# terra_o_verde_placa_perfurada_com_pluvio.net
KiCad netlist of a schematic drawn in EAGLE
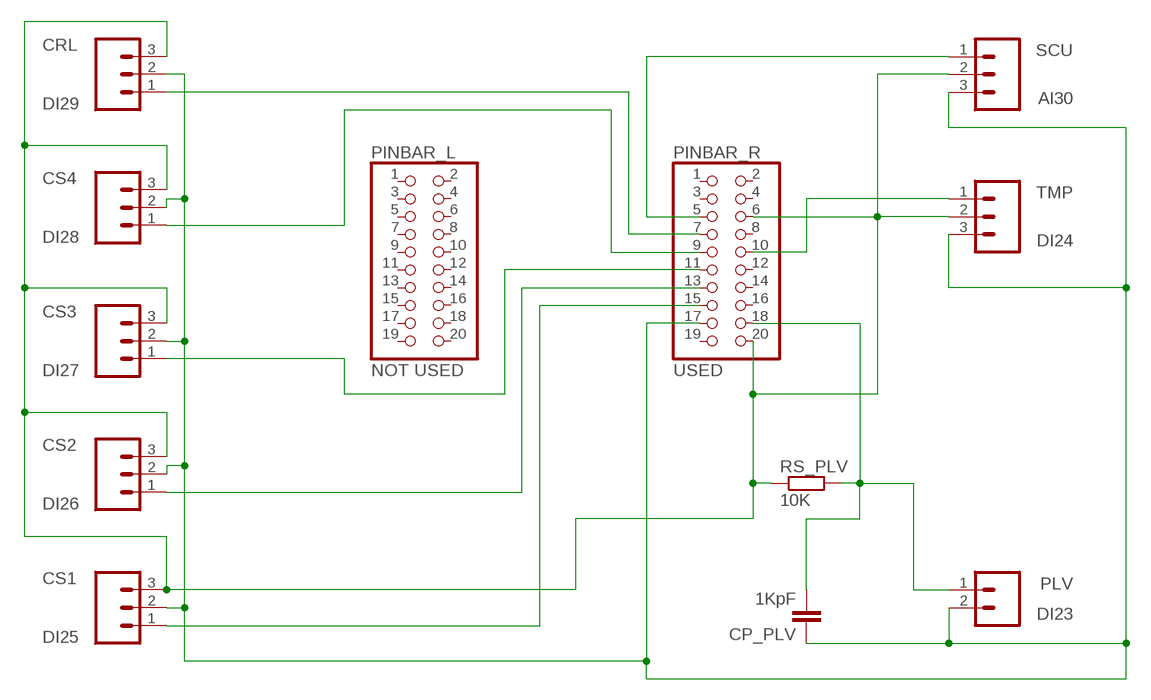
[diagram p0: schematic, sheet 1]

(export (version "E")
  (design (tool "Eeschema 10.0.6"))
  (components
    (comp (ref "CP_PLV")
      (value "1KpF")
      (footprint "eagle-import:C025-024X044")
      (libsource (lib "eagle-import") (part "C-EU025-024X044"))
    )
    (comp (ref "CRL")
      (value "DI29")
      (footprint "eagle-import:03P")
      (libsource (lib "eagle-import") (part "M03"))
    )
    (comp (ref "CS1")
      (value "DI25")
      (footprint "eagle-import:03P")
      (libsource (lib "eagle-import") (part "M03"))
    )
    (comp (ref "CS2")
      (value "DI26")
      (footprint "eagle-import:03P")
      (libsource (lib "eagle-import") (part "M03"))
    )
    (comp (ref "CS3")
      (value "DI27")
      (footprint "eagle-import:03P")
      (libsource (lib "eagle-import") (part "M03"))
    )
    (comp (ref "CS4")
      (value "DI28")
      (footprint "eagle-import:03P")
      (libsource (lib "eagle-import") (part "M03"))
    )
    (comp (ref "PINBAR_L")
      (value "NOT USED")
      (footprint "eagle-import:2X10")
      (libsource (lib "eagle-import") (part "PINHD-2X10"))
    )
    (comp (ref "PINBAR_R")
      (value "USED")
      (footprint "eagle-import:2X10")
      (libsource (lib "eagle-import") (part "PINHD-2X10"))
    )
    (comp (ref "PLV")
      (value "DI23")
      (footprint "eagle-import:02P")
      (libsource (lib "eagle-import") (part "M02"))
    )
    (comp (ref "RS_PLV")
      (value "10K")
      (footprint "eagle-import:0207_7")
      (libsource (lib "eagle-import") (part "R-EU_0207/7"))
    )
    (comp (ref "SCU")
      (value "AI30")
      (footprint "eagle-import:03P")
      (libsource (lib "eagle-import") (part "M03"))
    )
    (comp (ref "TMP")
      (value "DI24")
      (footprint "eagle-import:03P")
      (libsource (lib "eagle-import") (part "M03"))
    )
  )
  (nets
    (net (code "1") (name "Net-(CP_PLV-Pad1)") (class "Default")
      (node (ref "CP_PLV") (pin "1") (pinfunction "1_1") (pintype "passive"))
      (node (ref "CRL") (pin "2") (pinfunction "2_2") (pintype "passive"))
      (node (ref "CS1") (pin "2") (pinfunction "2_2") (pintype "passive"))
      (node (ref "CS2") (pin "2") (pinfunction "2_2") (pintype "passive"))
      (node (ref "CS3") (pin "2") (pinfunction "2_2") (pintype "passive"))
      (node (ref "CS4") (pin "2") (pinfunction "2_2") (pintype "passive"))
      (node (ref "PINBAR_R") (pin "17") (pinfunction "17_17") (pintype "passive"))
      (node (ref "PLV") (pin "2") (pinfunction "2_2") (pintype "passive"))
      (node (ref "SCU") (pin "3") (pinfunction "3_3") (pintype "passive"))
      (node (ref "TMP") (pin "3") (pinfunction "3_3") (pintype "passive"))
    )
    (net (code "2") (name "Net-(CP_PLV-Pad2)") (class "Default")
      (node (ref "CP_PLV") (pin "2") (pinfunction "2_2") (pintype "passive"))
      (node (ref "PINBAR_R") (pin "18") (pinfunction "18_18") (pintype "passive"))
      (node (ref "PLV") (pin "1") (pinfunction "1_1") (pintype "passive"))
      (node (ref "RS_PLV") (pin "2") (pinfunction "2_2") (pintype "passive"))
    )
    (net (code "3") (name "Net-(CRL-Pad1)") (class "Default")
      (node (ref "CRL") (pin "1") (pinfunction "1_1") (pintype "passive"))
      (node (ref "PINBAR_R") (pin "7") (pinfunction "7_7") (pintype "passive"))
    )
    (net (code "4") (name "Net-(CRL-Pad3)") (class "Default")
      (node (ref "CRL") (pin "3") (pinfunction "3_3") (pintype "passive"))
      (node (ref "CS1") (pin "3") (pinfunction "3_3") (pintype "passive"))
      (node (ref "CS2") (pin "3") (pinfunction "3_3") (pintype "passive"))
      (node (ref "CS3") (pin "3") (pinfunction "3_3") (pintype "passive"))
      (node (ref "CS4") (pin "3") (pinfunction "3_3") (pintype "passive"))
      (node (ref "PINBAR_R") (pin "20") (pinfunction "20_20") (pintype "passive"))
      (node (ref "PINBAR_R") (pin "6") (pinfunction "6_6") (pintype "passive"))
      (node (ref "RS_PLV") (pin "1") (pinfunction "1_1") (pintype "passive"))
      (node (ref "SCU") (pin "2") (pinfunction "2_2") (pintype "passive"))
      (node (ref "TMP") (pin "2") (pinfunction "2_2") (pintype "passive"))
    )
    (net (code "5") (name "Net-(CS1-Pad1)") (class "Default")
      (node (ref "CS1") (pin "1") (pinfunction "1_1") (pintype "passive"))
      (node (ref "PINBAR_R") (pin "15") (pinfunction "15_15") (pintype "passive"))
    )
    (net (code "6") (name "Net-(CS2-Pad1)") (class "Default")
      (node (ref "CS2") (pin "1") (pinfunction "1_1") (pintype "passive"))
      (node (ref "PINBAR_R") (pin "13") (pinfunction "13_13") (pintype "passive"))
    )
    (net (code "7") (name "Net-(CS3-Pad1)") (class "Default")
      (node (ref "CS3") (pin "1") (pinfunction "1_1") (pintype "passive"))
      (node (ref "PINBAR_R") (pin "11") (pinfunction "11_11") (pintype "passive"))
    )
    (net (code "8") (name "Net-(CS4-Pad1)") (class "Default")
      (node (ref "CS4") (pin "1") (pinfunction "1_1") (pintype "passive"))
      (node (ref "PINBAR_R") (pin "9") (pinfunction "9_9") (pintype "passive"))
    )
    (net (code "9") (name "Net-(PINBAR_R-Pad5)") (class "Default")
      (node (ref "PINBAR_R") (pin "5") (pinfunction "5_5") (pintype "passive"))
      (node (ref "SCU") (pin "1") (pinfunction "1_1") (pintype "passive"))
    )
    (net (code "10") (name "Net-(PINBAR_R-Pad10)") (class "Default")
      (node (ref "PINBAR_R") (pin "10") (pinfunction "10_10") (pintype "passive"))
      (node (ref "TMP") (pin "1") (pinfunction "1_1") (pintype "passive"))
    )
    (net (code "11") (name "unconnected-(PINBAR_L-Pad1)") (class "Default")
      (node (ref "PINBAR_L") (pin "1") (pinfunction "1_1") (pintype "passive"))
    )
    (net (code "12") (name "unconnected-(PINBAR_L-Pad2)") (class "Default")
      (node (ref "PINBAR_L") (pin "2") (pinfunction "2_2") (pintype "passive"))
    )
    (net (code "13") (name "unconnected-(PINBAR_L-Pad3)") (class "Default")
      (node (ref "PINBAR_L") (pin "3") (pinfunction "3_3") (pintype "passive"))
    )
    (net (code "14") (name "unconnected-(PINBAR_L-Pad4)") (class "Default")
      (node (ref "PINBAR_L") (pin "4") (pinfunction "4_4") (pintype "passive"))
    )
    (net (code "15") (name "unconnected-(PINBAR_L-Pad5)") (class "Default")
      (node (ref "PINBAR_L") (pin "5") (pinfunction "5_5") (pintype "passive"))
    )
    (net (code "16") (name "unconnected-(PINBAR_L-Pad6)") (class "Default")
      (node (ref "PINBAR_L") (pin "6") (pinfunction "6_6") (pintype "passive"))
    )
    (net (code "17") (name "unconnected-(PINBAR_L-Pad7)") (class "Default")
      (node (ref "PINBAR_L") (pin "7") (pinfunction "7_7") (pintype "passive"))
    )
    (net (code "18") (name "unconnected-(PINBAR_L-Pad8)") (class "Default")
      (node (ref "PINBAR_L") (pin "8") (pinfunction "8_8") (pintype "passive"))
    )
    (net (code "19") (name "unconnected-(PINBAR_L-Pad9)") (class "Default")
      (node (ref "PINBAR_L") (pin "9") (pinfunction "9_9") (pintype "passive"))
    )
    (net (code "20") (name "unconnected-(PINBAR_L-Pad10)") (class "Default")
      (node (ref "PINBAR_L") (pin "10") (pinfunction "10_10") (pintype "passive"))
    )
    (net (code "21") (name "unconnected-(PINBAR_L-Pad11)") (class "Default")
      (node (ref "PINBAR_L") (pin "11") (pinfunction "11_11") (pintype "passive"))
    )
    (net (code "22") (name "unconnected-(PINBAR_L-Pad12)") (class "Default")
      (node (ref "PINBAR_L") (pin "12") (pinfunction "12_12") (pintype "passive"))
    )
    (net (code "23") (name "unconnected-(PINBAR_L-Pad13)") (class "Default")
      (node (ref "PINBAR_L") (pin "13") (pinfunction "13_13") (pintype "passive"))
    )
    (net (code "24") (name "unconnected-(PINBAR_L-Pad14)") (class "Default")
      (node (ref "PINBAR_L") (pin "14") (pinfunction "14_14") (pintype "passive"))
    )
    (net (code "25") (name "unconnected-(PINBAR_L-Pad15)") (class "Default")
      (node (ref "PINBAR_L") (pin "15") (pinfunction "15_15") (pintype "passive"))
    )
    (net (code "26") (name "unconnected-(PINBAR_L-Pad16)") (class "Default")
      (node (ref "PINBAR_L") (pin "16") (pinfunction "16_16") (pintype "passive"))
    )
    (net (code "27") (name "unconnected-(PINBAR_L-Pad17)") (class "Default")
      (node (ref "PINBAR_L") (pin "17") (pinfunction "17_17") (pintype "passive"))
    )
    (net (code "28") (name "unconnected-(PINBAR_L-Pad18)") (class "Default")
      (node (ref "PINBAR_L") (pin "18") (pinfunction "18_18") (pintype "passive"))
    )
    (net (code "29") (name "unconnected-(PINBAR_L-Pad19)") (class "Default")
      (node (ref "PINBAR_L") (pin "19") (pinfunction "19_19") (pintype "passive"))
    )
    (net (code "30") (name "unconnected-(PINBAR_L-Pad20)") (class "Default")
      (node (ref "PINBAR_L") (pin "20") (pinfunction "20_20") (pintype "passive"))
    )
    (net (code "31") (name "unconnected-(PINBAR_R-Pad1)") (class "Default")
      (node (ref "PINBAR_R") (pin "1") (pinfunction "1_1") (pintype "passive"))
    )
    (net (code "32") (name "unconnected-(PINBAR_R-Pad2)") (class "Default")
      (node (ref "PINBAR_R") (pin "2") (pinfunction "2_2") (pintype "passive"))
    )
    (net (code "33") (name "unconnected-(PINBAR_R-Pad3)") (class "Default")
      (node (ref "PINBAR_R") (pin "3") (pinfunction "3_3") (pintype "passive"))
    )
    (net (code "34") (name "unconnected-(PINBAR_R-Pad4)") (class "Default")
      (node (ref "PINBAR_R") (pin "4") (pinfunction "4_4") (pintype "passive"))
    )
    (net (code "35") (name "unconnected-(PINBAR_R-Pad8)") (class "Default")
      (node (ref "PINBAR_R") (pin "8") (pinfunction "8_8") (pintype "passive"))
    )
    (net (code "36") (name "unconnected-(PINBAR_R-Pad12)") (class "Default")
      (node (ref "PINBAR_R") (pin "12") (pinfunction "12_12") (pintype "passive"))
    )
    (net (code "37") (name "unconnected-(PINBAR_R-Pad14)") (class "Default")
      (node (ref "PINBAR_R") (pin "14") (pinfunction "14_14") (pintype "passive"))
    )
    (net (code "38") (name "unconnected-(PINBAR_R-Pad16)") (class "Default")
      (node (ref "PINBAR_R") (pin "16") (pinfunction "16_16") (pintype "passive"))
    )
    (net (code "39") (name "unconnected-(PINBAR_R-Pad19)") (class "Default")
      (node (ref "PINBAR_R") (pin "19") (pinfunction "19_19") (pintype "passive"))
    )
  )
)
